# Simple-Bug-BC547.net
KiCad netlist of a schematic drawn in EAGLE
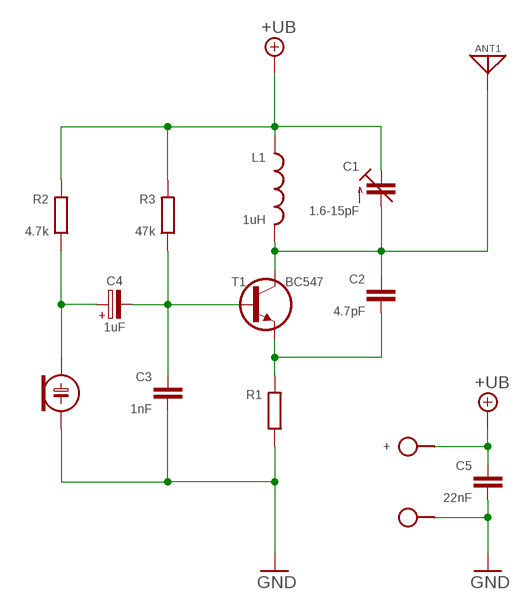
[diagram p0: schematic, sheet 1]

(export (version "E")
  (design (tool "Eeschema 10.0.6"))
  (components
    (comp (ref "+")
      (value "SPAD")
      (footprint "eagle-import:SPAD")
      (libsource (lib "eagle-import") (part "SPAD"))
    )
    (comp (ref "ANT1")
      (value "ANT")
      (footprint "eagle-import:SPAD")
      (libsource (lib "eagle-import") (part "ANT"))
    )
    (comp (ref "C1")
      (value "1.6-15pF")
      (footprint "eagle-import:TRIM-2222-808")
      (libsource (lib "eagle-import") (part "C-TR-PH20127"))
    )
    (comp (ref "C2")
      (value "4.7pF")
      (footprint "eagle-import:C050-020X036")
      (libsource (lib "eagle-import") (part "C050-020X036"))
    )
    (comp (ref "C3")
      (value "1nF")
      (footprint "eagle-import:C050-020X036_V")
      (libsource (lib "eagle-import") (part "C050-020X036/V"))
    )
    (comp (ref "C4")
      (value "1uF")
      (footprint "eagle-import:E2,5-3")
      (libsource (lib "eagle-import") (part "CPOLE2,5-3"))
    )
    (comp (ref "C5")
      (value "22nF")
      (footprint "eagle-import:C050-020X036")
      (libsource (lib "eagle-import") (part "C050-020X036"))
    )
    (comp (ref "ECM")
      (value "ECM-4")
      (footprint "eagle-import:ECM-4")
      (libsource (lib "eagle-import") (part "ECM-4"))
    )
    (comp (ref "L1")
      (value "1uH")
      (footprint "eagle-import:L-04_7V")
      (libsource (lib "eagle-import") (part "L04/7"))
    )
    (comp (ref "R1")
      (value "R0202/5")
      (footprint "eagle-import:0202_5")
      (libsource (lib "eagle-import") (part "R0202/5"))
    )
    (comp (ref "R2")
      (value "4.7k")
      (footprint "eagle-import:0202_5")
      (libsource (lib "eagle-import") (part "R0202/5"))
    )
    (comp (ref "R3")
      (value "47k")
      (footprint "eagle-import:0202_5")
      (libsource (lib "eagle-import") (part "R0202/5"))
    )
    (comp (ref "T1")
      (value "BC547")
      (footprint "eagle-import:TO92-CBE-A")
      (libsource (lib "eagle-import") (part "BC547CBE-A"))
    )
    (comp (ref "̶̶")
      (value "SPAD")
      (footprint "eagle-import:SPAD")
      (libsource (lib "eagle-import") (part "SPAD"))
    )
  )
  (nets
    (net (code "1") (name "+UB") (class "Default")
      (node (ref "+") (pin "1") (pinfunction "P$1_1") (pintype "bidirectional"))
      (node (ref "C1") (pin "1") (pinfunction "E_1") (pintype "passive"))
      (node (ref "C1") (pin "3") (pinfunction "E_3") (pintype "passive"))
      (node (ref "C5") (pin "1") (pinfunction "1_1") (pintype "passive"))
      (node (ref "L1") (pin "1") (pinfunction "1_1") (pintype "passive"))
      (node (ref "R2") (pin "2") (pinfunction "2_2") (pintype "passive"))
      (node (ref "R3") (pin "2") (pinfunction "2_2") (pintype "passive"))
    )
    (net (code "2") (name "GND") (class "Default")
      (node (ref "C3") (pin "2") (pinfunction "2_2") (pintype "passive"))
      (node (ref "C5") (pin "2") (pinfunction "2_2") (pintype "passive"))
      (node (ref "ECM") (pin "2") (pinfunction "-_2") (pintype "passive"))
      (node (ref "R1") (pin "1") (pinfunction "1_1") (pintype "passive"))
      (node (ref "̶̶") (pin "1") (pinfunction "P$1_1") (pintype "bidirectional"))
    )
    (net (code "3") (name "Net-(C1-A)") (class "Default")
      (node (ref "ANT1") (pin "1") (pinfunction "1_1") (pintype "output"))
      (node (ref "C1") (pin "2") (pinfunction "A_2") (pintype "passive"))
      (node (ref "C2") (pin "1") (pinfunction "1_1") (pintype "passive"))
      (node (ref "L1") (pin "2") (pinfunction "2_2") (pintype "passive"))
      (node (ref "T1") (pin "C") (pinfunction "C_C") (pintype "passive"))
    )
    (net (code "4") (name "Net-(C2-Pad2)") (class "Default")
      (node (ref "C2") (pin "2") (pinfunction "2_2") (pintype "passive"))
      (node (ref "R1") (pin "2") (pinfunction "2_2") (pintype "passive"))
      (node (ref "T1") (pin "E") (pinfunction "E_E") (pintype "passive"))
    )
    (net (code "5") (name "Net-(C3-Pad1)") (class "Default")
      (node (ref "C3") (pin "1") (pinfunction "1_1") (pintype "passive"))
      (node (ref "C4") (pin "-") (pinfunction "-_-") (pintype "passive"))
      (node (ref "R3") (pin "1") (pinfunction "1_1") (pintype "passive"))
      (node (ref "T1") (pin "B") (pinfunction "B_B") (pintype "passive"))
    )
    (net (code "6") (name "Net-(ECM-+)") (class "Default")
      (node (ref "C4") (pin "+") (pinfunction "+_+") (pintype "passive"))
      (node (ref "ECM") (pin "1") (pinfunction "+_1") (pintype "passive"))
      (node (ref "R2") (pin "1") (pinfunction "1_1") (pintype "passive"))
    )
  )
)
